# Schematic.net
KiCad netlist of a schematic drawn in Altium Designer
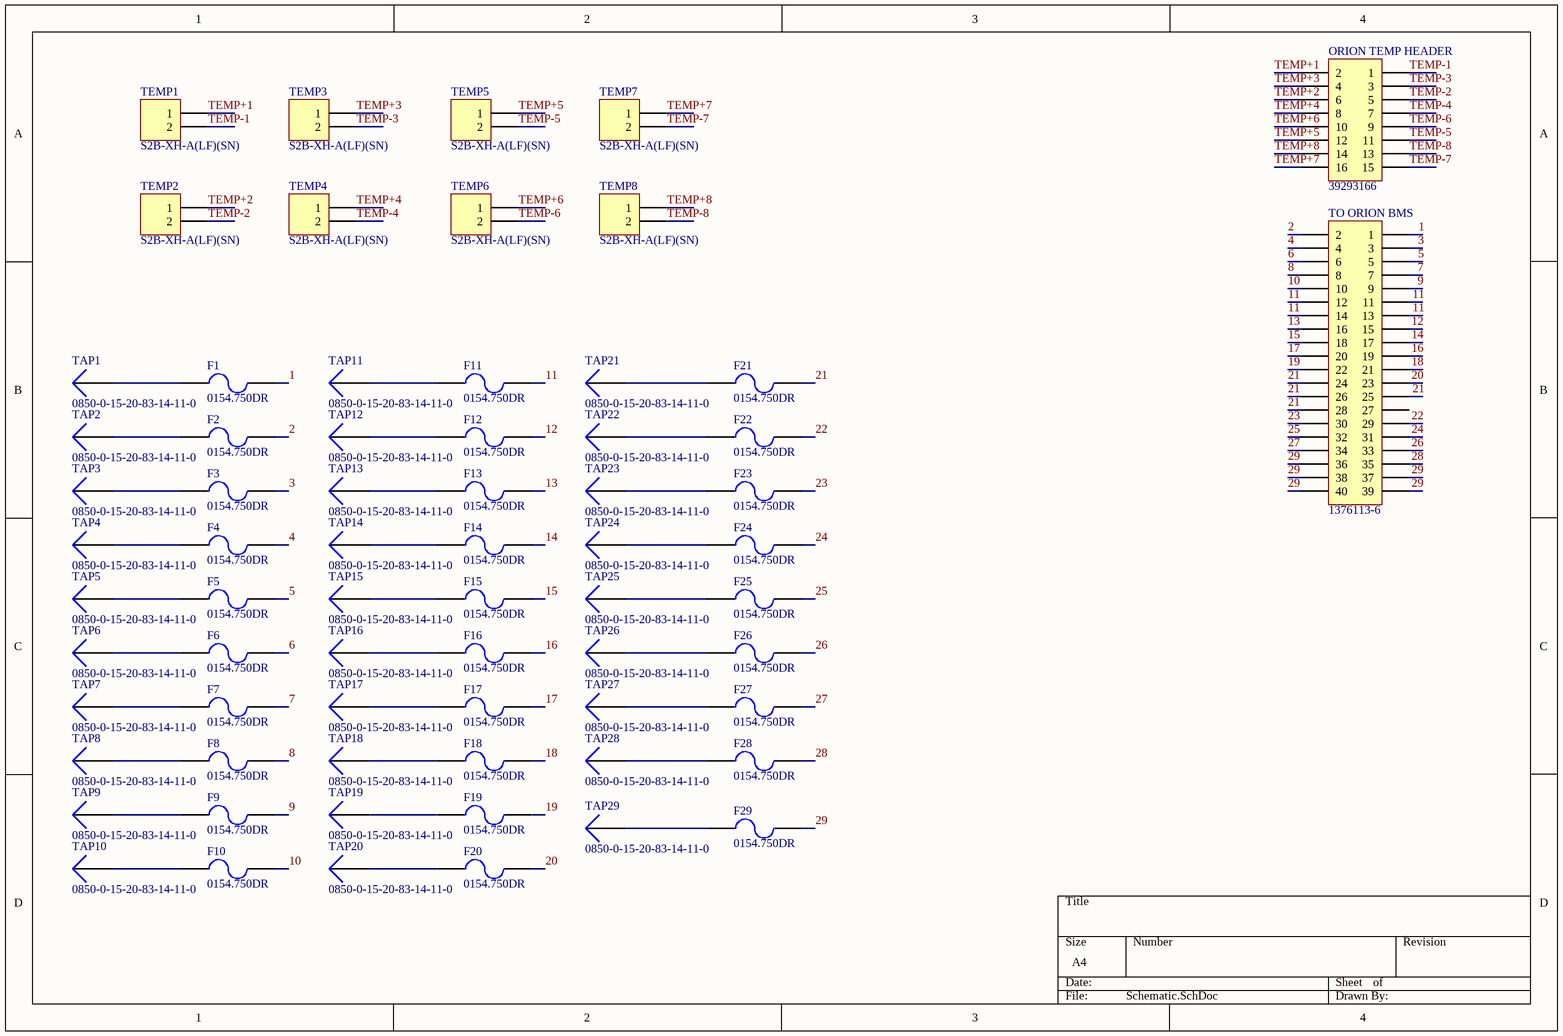
[diagram p0: Schematic.SchDoc]

(export (version "E")
  (design (tool "Eeschema 10.0.6"))
  (components
    (comp (ref "F1")
      (value "0154.750DR")
      (footprint "Omni BLOK 0154")
      (description "FUSE BOARD MNT 750MA 125VAC/VDC")
      (fields
        (field (name "MANUFACTURER") "LittelFuse Inc")
        (field (name "DIGIKEY PART NUMBER") "F1221CT-ND")
      )
      (libsource (lib "ts_20-standard-library") (part "Fuse"))
    )
    (comp (ref "F2")
      (value "0154.750DR")
      (footprint "Omni BLOK 0154")
      (description "FUSE BOARD MNT 750MA 125VAC/VDC")
      (fields
        (field (name "MANUFACTURER") "LittelFuse Inc")
        (field (name "DIGIKEY PART NUMBER") "F1221CT-ND")
      )
      (libsource (lib "ts_20-standard-library") (part "Fuse"))
    )
    (comp (ref "F3")
      (value "0154.750DR")
      (footprint "Omni BLOK 0154")
      (description "FUSE BOARD MNT 750MA 125VAC/VDC")
      (fields
        (field (name "MANUFACTURER") "LittelFuse Inc")
        (field (name "DIGIKEY PART NUMBER") "F1221CT-ND")
      )
      (libsource (lib "ts_20-standard-library") (part "Fuse"))
    )
    (comp (ref "F4")
      (value "0154.750DR")
      (footprint "Omni BLOK 0154")
      (description "FUSE BOARD MNT 750MA 125VAC/VDC")
      (fields
        (field (name "MANUFACTURER") "LittelFuse Inc")
        (field (name "DIGIKEY PART NUMBER") "F1221CT-ND")
      )
      (libsource (lib "ts_20-standard-library") (part "Fuse"))
    )
    (comp (ref "F5")
      (value "0154.750DR")
      (footprint "Omni BLOK 0154")
      (description "FUSE BOARD MNT 750MA 125VAC/VDC")
      (fields
        (field (name "MANUFACTURER") "LittelFuse Inc")
        (field (name "DIGIKEY PART NUMBER") "F1221CT-ND")
      )
      (libsource (lib "ts_20-standard-library") (part "Fuse"))
    )
    (comp (ref "F6")
      (value "0154.750DR")
      (footprint "Omni BLOK 0154")
      (description "FUSE BOARD MNT 750MA 125VAC/VDC")
      (fields
        (field (name "MANUFACTURER") "LittelFuse Inc")
        (field (name "DIGIKEY PART NUMBER") "F1221CT-ND")
      )
      (libsource (lib "ts_20-standard-library") (part "Fuse"))
    )
    (comp (ref "F7")
      (value "0154.750DR")
      (footprint "Omni BLOK 0154")
      (description "FUSE BOARD MNT 750MA 125VAC/VDC")
      (fields
        (field (name "MANUFACTURER") "LittelFuse Inc")
        (field (name "DIGIKEY PART NUMBER") "F1221CT-ND")
      )
      (libsource (lib "ts_20-standard-library") (part "Fuse"))
    )
    (comp (ref "F8")
      (value "0154.750DR")
      (footprint "Omni BLOK 0154")
      (description "FUSE BOARD MNT 750MA 125VAC/VDC")
      (fields
        (field (name "MANUFACTURER") "LittelFuse Inc")
        (field (name "DIGIKEY PART NUMBER") "F1221CT-ND")
      )
      (libsource (lib "ts_20-standard-library") (part "Fuse"))
    )
    (comp (ref "F9")
      (value "0154.750DR")
      (footprint "Omni BLOK 0154")
      (description "FUSE BOARD MNT 750MA 125VAC/VDC")
      (fields
        (field (name "MANUFACTURER") "LittelFuse Inc")
        (field (name "DIGIKEY PART NUMBER") "F1221CT-ND")
      )
      (libsource (lib "ts_20-standard-library") (part "Fuse"))
    )
    (comp (ref "F10")
      (value "0154.750DR")
      (footprint "Omni BLOK 0154")
      (description "FUSE BOARD MNT 750MA 125VAC/VDC")
      (fields
        (field (name "MANUFACTURER") "LittelFuse Inc")
        (field (name "DIGIKEY PART NUMBER") "F1221CT-ND")
      )
      (libsource (lib "ts_20-standard-library") (part "Fuse"))
    )
    (comp (ref "F11")
      (value "0154.750DR")
      (footprint "Omni BLOK 0154")
      (description "FUSE BOARD MNT 750MA 125VAC/VDC")
      (fields
        (field (name "MANUFACTURER") "LittelFuse Inc")
        (field (name "DIGIKEY PART NUMBER") "F1221CT-ND")
      )
      (libsource (lib "ts_20-standard-library") (part "Fuse"))
    )
    (comp (ref "F12")
      (value "0154.750DR")
      (footprint "Omni BLOK 0154")
      (description "FUSE BOARD MNT 750MA 125VAC/VDC")
      (fields
        (field (name "MANUFACTURER") "LittelFuse Inc")
        (field (name "DIGIKEY PART NUMBER") "F1221CT-ND")
      )
      (libsource (lib "ts_20-standard-library") (part "Fuse"))
    )
    (comp (ref "F13")
      (value "0154.750DR")
      (footprint "Omni BLOK 0154")
      (description "FUSE BOARD MNT 750MA 125VAC/VDC")
      (fields
        (field (name "MANUFACTURER") "LittelFuse Inc")
        (field (name "DIGIKEY PART NUMBER") "F1221CT-ND")
      )
      (libsource (lib "ts_20-standard-library") (part "Fuse"))
    )
    (comp (ref "F14")
      (value "0154.750DR")
      (footprint "Omni BLOK 0154")
      (description "FUSE BOARD MNT 750MA 125VAC/VDC")
      (fields
        (field (name "MANUFACTURER") "LittelFuse Inc")
        (field (name "DIGIKEY PART NUMBER") "F1221CT-ND")
      )
      (libsource (lib "ts_20-standard-library") (part "Fuse"))
    )
    (comp (ref "F15")
      (value "0154.750DR")
      (footprint "Omni BLOK 0154")
      (description "FUSE BOARD MNT 750MA 125VAC/VDC")
      (fields
        (field (name "MANUFACTURER") "LittelFuse Inc")
        (field (name "DIGIKEY PART NUMBER") "F1221CT-ND")
      )
      (libsource (lib "ts_20-standard-library") (part "Fuse"))
    )
    (comp (ref "F16")
      (value "0154.750DR")
      (footprint "Omni BLOK 0154")
      (description "FUSE BOARD MNT 750MA 125VAC/VDC")
      (fields
        (field (name "MANUFACTURER") "LittelFuse Inc")
        (field (name "DIGIKEY PART NUMBER") "F1221CT-ND")
      )
      (libsource (lib "ts_20-standard-library") (part "Fuse"))
    )
    (comp (ref "F17")
      (value "0154.750DR")
      (footprint "Omni BLOK 0154")
      (description "FUSE BOARD MNT 750MA 125VAC/VDC")
      (fields
        (field (name "MANUFACTURER") "LittelFuse Inc")
        (field (name "DIGIKEY PART NUMBER") "F1221CT-ND")
      )
      (libsource (lib "ts_20-standard-library") (part "Fuse"))
    )
    (comp (ref "F18")
      (value "0154.750DR")
      (footprint "Omni BLOK 0154")
      (description "FUSE BOARD MNT 750MA 125VAC/VDC")
      (fields
        (field (name "MANUFACTURER") "LittelFuse Inc")
        (field (name "DIGIKEY PART NUMBER") "F1221CT-ND")
      )
      (libsource (lib "ts_20-standard-library") (part "Fuse"))
    )
    (comp (ref "F19")
      (value "0154.750DR")
      (footprint "Omni BLOK 0154")
      (description "FUSE BOARD MNT 750MA 125VAC/VDC")
      (fields
        (field (name "MANUFACTURER") "LittelFuse Inc")
        (field (name "DIGIKEY PART NUMBER") "F1221CT-ND")
      )
      (libsource (lib "ts_20-standard-library") (part "Fuse"))
    )
    (comp (ref "F20")
      (value "0154.750DR")
      (footprint "Omni BLOK 0154")
      (description "FUSE BOARD MNT 750MA 125VAC/VDC")
      (fields
        (field (name "MANUFACTURER") "LittelFuse Inc")
        (field (name "DIGIKEY PART NUMBER") "F1221CT-ND")
      )
      (libsource (lib "ts_20-standard-library") (part "Fuse"))
    )
    (comp (ref "F21")
      (value "0154.750DR")
      (footprint "Omni BLOK 0154")
      (description "FUSE BOARD MNT 750MA 125VAC/VDC")
      (fields
        (field (name "MANUFACTURER") "LittelFuse Inc")
        (field (name "DIGIKEY PART NUMBER") "F1221CT-ND")
      )
      (libsource (lib "ts_20-standard-library") (part "Fuse"))
    )
    (comp (ref "F22")
      (value "0154.750DR")
      (footprint "Omni BLOK 0154")
      (description "FUSE BOARD MNT 750MA 125VAC/VDC")
      (fields
        (field (name "MANUFACTURER") "LittelFuse Inc")
        (field (name "DIGIKEY PART NUMBER") "F1221CT-ND")
      )
      (libsource (lib "ts_20-standard-library") (part "Fuse"))
    )
    (comp (ref "F23")
      (value "0154.750DR")
      (footprint "Omni BLOK 0154")
      (description "FUSE BOARD MNT 750MA 125VAC/VDC")
      (fields
        (field (name "MANUFACTURER") "LittelFuse Inc")
        (field (name "DIGIKEY PART NUMBER") "F1221CT-ND")
      )
      (libsource (lib "ts_20-standard-library") (part "Fuse"))
    )
    (comp (ref "F24")
      (value "0154.750DR")
      (footprint "Omni BLOK 0154")
      (description "FUSE BOARD MNT 750MA 125VAC/VDC")
      (fields
        (field (name "MANUFACTURER") "LittelFuse Inc")
        (field (name "DIGIKEY PART NUMBER") "F1221CT-ND")
      )
      (libsource (lib "ts_20-standard-library") (part "Fuse"))
    )
    (comp (ref "F25")
      (value "0154.750DR")
      (footprint "Omni BLOK 0154")
      (description "FUSE BOARD MNT 750MA 125VAC/VDC")
      (fields
        (field (name "MANUFACTURER") "LittelFuse Inc")
        (field (name "DIGIKEY PART NUMBER") "F1221CT-ND")
      )
      (libsource (lib "ts_20-standard-library") (part "Fuse"))
    )
    (comp (ref "F26")
      (value "0154.750DR")
      (footprint "Omni BLOK 0154")
      (description "FUSE BOARD MNT 750MA 125VAC/VDC")
      (fields
        (field (name "MANUFACTURER") "LittelFuse Inc")
        (field (name "DIGIKEY PART NUMBER") "F1221CT-ND")
      )
      (libsource (lib "ts_20-standard-library") (part "Fuse"))
    )
    (comp (ref "F27")
      (value "0154.750DR")
      (footprint "Omni BLOK 0154")
      (description "FUSE BOARD MNT 750MA 125VAC/VDC")
      (fields
        (field (name "MANUFACTURER") "LittelFuse Inc")
        (field (name "DIGIKEY PART NUMBER") "F1221CT-ND")
      )
      (libsource (lib "ts_20-standard-library") (part "Fuse"))
    )
    (comp (ref "F28")
      (value "0154.750DR")
      (footprint "Omni BLOK 0154")
      (description "FUSE BOARD MNT 750MA 125VAC/VDC")
      (fields
        (field (name "MANUFACTURER") "LittelFuse Inc")
        (field (name "DIGIKEY PART NUMBER") "F1221CT-ND")
      )
      (libsource (lib "ts_20-standard-library") (part "Fuse"))
    )
    (comp (ref "F29")
      (value "0154.750DR")
      (footprint "Omni BLOK 0154")
      (description "FUSE BOARD MNT 750MA 125VAC/VDC")
      (fields
        (field (name "MANUFACTURER") "LittelFuse Inc")
        (field (name "DIGIKEY PART NUMBER") "F1221CT-ND")
      )
      (libsource (lib "ts_20-standard-library") (part "Fuse"))
    )
    (comp (ref "ORION TEMP HEADER")
      (value "39293166")
      (footprint "39293166")
      (fields (field (name "DIGIKEY PART NUMBER") "WM3850-ND") (field (name "CONTACT") "Tin"))
      (libsource (lib "ts_20-standard-connectors") (part "16"))
    )
    (comp (ref "TAP1")
      (value "0850-0-15-20-83-14-11-0")
      (footprint "0850-0-15-20-83-14-11-0")
      (fields (field (name "DIGIKEY PART NUMBER") "ED90436-ND") (field (name "CONTACT") "Gold"))
      (libsource (lib "ts_20-standard-connectors") (part "0850-0-15-20-83-14-11-0"))
    )
    (comp (ref "TAP2")
      (value "0850-0-15-20-83-14-11-0")
      (footprint "0850-0-15-20-83-14-11-0")
      (fields (field (name "DIGIKEY PART NUMBER") "ED90436-ND") (field (name "CONTACT") "Gold"))
      (libsource (lib "ts_20-standard-connectors") (part "0850-0-15-20-83-14-11-0"))
    )
    (comp (ref "TAP3")
      (value "0850-0-15-20-83-14-11-0")
      (footprint "0850-0-15-20-83-14-11-0")
      (fields (field (name "DIGIKEY PART NUMBER") "ED90436-ND") (field (name "CONTACT") "Gold"))
      (libsource (lib "ts_20-standard-connectors") (part "0850-0-15-20-83-14-11-0"))
    )
    (comp (ref "TAP4")
      (value "0850-0-15-20-83-14-11-0")
      (footprint "0850-0-15-20-83-14-11-0")
      (fields (field (name "DIGIKEY PART NUMBER") "ED90436-ND") (field (name "CONTACT") "Gold"))
      (libsource (lib "ts_20-standard-connectors") (part "0850-0-15-20-83-14-11-0"))
    )
    (comp (ref "TAP5")
      (value "0850-0-15-20-83-14-11-0")
      (footprint "0850-0-15-20-83-14-11-0")
      (fields (field (name "DIGIKEY PART NUMBER") "ED90436-ND") (field (name "CONTACT") "Gold"))
      (libsource (lib "ts_20-standard-connectors") (part "0850-0-15-20-83-14-11-0"))
    )
    (comp (ref "TAP6")
      (value "0850-0-15-20-83-14-11-0")
      (footprint "0850-0-15-20-83-14-11-0")
      (fields (field (name "DIGIKEY PART NUMBER") "ED90436-ND") (field (name "CONTACT") "Gold"))
      (libsource (lib "ts_20-standard-connectors") (part "0850-0-15-20-83-14-11-0"))
    )
    (comp (ref "TAP7")
      (value "0850-0-15-20-83-14-11-0")
      (footprint "0850-0-15-20-83-14-11-0")
      (fields (field (name "DIGIKEY PART NUMBER") "ED90436-ND") (field (name "CONTACT") "Gold"))
      (libsource (lib "ts_20-standard-connectors") (part "0850-0-15-20-83-14-11-0"))
    )
    (comp (ref "TAP8")
      (value "0850-0-15-20-83-14-11-0")
      (footprint "0850-0-15-20-83-14-11-0")
      (fields (field (name "DIGIKEY PART NUMBER") "ED90436-ND") (field (name "CONTACT") "Gold"))
      (libsource (lib "ts_20-standard-connectors") (part "0850-0-15-20-83-14-11-0"))
    )
    (comp (ref "TAP9")
      (value "0850-0-15-20-83-14-11-0")
      (footprint "0850-0-15-20-83-14-11-0")
      (fields (field (name "DIGIKEY PART NUMBER") "ED90436-ND") (field (name "CONTACT") "Gold"))
      (libsource (lib "ts_20-standard-connectors") (part "0850-0-15-20-83-14-11-0"))
    )
    (comp (ref "TAP10")
      (value "0850-0-15-20-83-14-11-0")
      (footprint "0850-0-15-20-83-14-11-0")
      (fields (field (name "DIGIKEY PART NUMBER") "ED90436-ND") (field (name "CONTACT") "Gold"))
      (libsource (lib "ts_20-standard-connectors") (part "0850-0-15-20-83-14-11-0"))
    )
    (comp (ref "TAP11")
      (value "0850-0-15-20-83-14-11-0")
      (footprint "0850-0-15-20-83-14-11-0")
      (fields (field (name "DIGIKEY PART NUMBER") "ED90436-ND") (field (name "CONTACT") "Gold"))
      (libsource (lib "ts_20-standard-connectors") (part "0850-0-15-20-83-14-11-0"))
    )
    (comp (ref "TAP12")
      (value "0850-0-15-20-83-14-11-0")
      (footprint "0850-0-15-20-83-14-11-0")
      (fields (field (name "DIGIKEY PART NUMBER") "ED90436-ND") (field (name "CONTACT") "Gold"))
      (libsource (lib "ts_20-standard-connectors") (part "0850-0-15-20-83-14-11-0"))
    )
    (comp (ref "TAP13")
      (value "0850-0-15-20-83-14-11-0")
      (footprint "0850-0-15-20-83-14-11-0")
      (fields (field (name "DIGIKEY PART NUMBER") "ED90436-ND") (field (name "CONTACT") "Gold"))
      (libsource (lib "ts_20-standard-connectors") (part "0850-0-15-20-83-14-11-0"))
    )
    (comp (ref "TAP14")
      (value "0850-0-15-20-83-14-11-0")
      (footprint "0850-0-15-20-83-14-11-0")
      (fields (field (name "DIGIKEY PART NUMBER") "ED90436-ND") (field (name "CONTACT") "Gold"))
      (libsource (lib "ts_20-standard-connectors") (part "0850-0-15-20-83-14-11-0"))
    )
    (comp (ref "TAP15")
      (value "0850-0-15-20-83-14-11-0")
      (footprint "0850-0-15-20-83-14-11-0")
      (fields (field (name "DIGIKEY PART NUMBER") "ED90436-ND") (field (name "CONTACT") "Gold"))
      (libsource (lib "ts_20-standard-connectors") (part "0850-0-15-20-83-14-11-0"))
    )
    (comp (ref "TAP16")
      (value "0850-0-15-20-83-14-11-0")
      (footprint "0850-0-15-20-83-14-11-0")
      (fields (field (name "DIGIKEY PART NUMBER") "ED90436-ND") (field (name "CONTACT") "Gold"))
      (libsource (lib "ts_20-standard-connectors") (part "0850-0-15-20-83-14-11-0"))
    )
    (comp (ref "TAP17")
      (value "0850-0-15-20-83-14-11-0")
      (footprint "0850-0-15-20-83-14-11-0")
      (fields (field (name "DIGIKEY PART NUMBER") "ED90436-ND") (field (name "CONTACT") "Gold"))
      (libsource (lib "ts_20-standard-connectors") (part "0850-0-15-20-83-14-11-0"))
    )
    (comp (ref "TAP18")
      (value "0850-0-15-20-83-14-11-0")
      (footprint "0850-0-15-20-83-14-11-0")
      (fields (field (name "DIGIKEY PART NUMBER") "ED90436-ND") (field (name "CONTACT") "Gold"))
      (libsource (lib "ts_20-standard-connectors") (part "0850-0-15-20-83-14-11-0"))
    )
    (comp (ref "TAP19")
      (value "0850-0-15-20-83-14-11-0")
      (footprint "0850-0-15-20-83-14-11-0")
      (fields (field (name "DIGIKEY PART NUMBER") "ED90436-ND") (field (name "CONTACT") "Gold"))
      (libsource (lib "ts_20-standard-connectors") (part "0850-0-15-20-83-14-11-0"))
    )
    (comp (ref "TAP20")
      (value "0850-0-15-20-83-14-11-0")
      (footprint "0850-0-15-20-83-14-11-0")
      (fields (field (name "DIGIKEY PART NUMBER") "ED90436-ND") (field (name "CONTACT") "Gold"))
      (libsource (lib "ts_20-standard-connectors") (part "0850-0-15-20-83-14-11-0"))
    )
    (comp (ref "TAP21")
      (value "0850-0-15-20-83-14-11-0")
      (footprint "0850-0-15-20-83-14-11-0")
      (fields (field (name "DIGIKEY PART NUMBER") "ED90436-ND") (field (name "CONTACT") "Gold"))
      (libsource (lib "ts_20-standard-connectors") (part "0850-0-15-20-83-14-11-0"))
    )
    (comp (ref "TAP22")
      (value "0850-0-15-20-83-14-11-0")
      (footprint "0850-0-15-20-83-14-11-0")
      (fields (field (name "DIGIKEY PART NUMBER") "ED90436-ND") (field (name "CONTACT") "Gold"))
      (libsource (lib "ts_20-standard-connectors") (part "0850-0-15-20-83-14-11-0"))
    )
    (comp (ref "TAP23")
      (value "0850-0-15-20-83-14-11-0")
      (footprint "0850-0-15-20-83-14-11-0")
      (fields (field (name "DIGIKEY PART NUMBER") "ED90436-ND") (field (name "CONTACT") "Gold"))
      (libsource (lib "ts_20-standard-connectors") (part "0850-0-15-20-83-14-11-0"))
    )
    (comp (ref "TAP24")
      (value "0850-0-15-20-83-14-11-0")
      (footprint "0850-0-15-20-83-14-11-0")
      (fields (field (name "DIGIKEY PART NUMBER") "ED90436-ND") (field (name "CONTACT") "Gold"))
      (libsource (lib "ts_20-standard-connectors") (part "0850-0-15-20-83-14-11-0"))
    )
    (comp (ref "TAP25")
      (value "0850-0-15-20-83-14-11-0")
      (footprint "0850-0-15-20-83-14-11-0")
      (fields (field (name "DIGIKEY PART NUMBER") "ED90436-ND") (field (name "CONTACT") "Gold"))
      (libsource (lib "ts_20-standard-connectors") (part "0850-0-15-20-83-14-11-0"))
    )
    (comp (ref "TAP26")
      (value "0850-0-15-20-83-14-11-0")
      (footprint "0850-0-15-20-83-14-11-0")
      (fields (field (name "DIGIKEY PART NUMBER") "ED90436-ND") (field (name "CONTACT") "Gold"))
      (libsource (lib "ts_20-standard-connectors") (part "0850-0-15-20-83-14-11-0"))
    )
    (comp (ref "TAP27")
      (value "0850-0-15-20-83-14-11-0")
      (footprint "0850-0-15-20-83-14-11-0")
      (fields (field (name "DIGIKEY PART NUMBER") "ED90436-ND") (field (name "CONTACT") "Gold"))
      (libsource (lib "ts_20-standard-connectors") (part "0850-0-15-20-83-14-11-0"))
    )
    (comp (ref "TAP28")
      (value "0850-0-15-20-83-14-11-0")
      (footprint "0850-0-15-20-83-14-11-0")
      (fields (field (name "DIGIKEY PART NUMBER") "ED90436-ND") (field (name "CONTACT") "Gold"))
      (libsource (lib "ts_20-standard-connectors") (part "0850-0-15-20-83-14-11-0"))
    )
    (comp (ref "TAP29")
      (value "0850-0-15-20-83-14-11-0")
      (footprint "0850-0-15-20-83-14-11-0")
      (fields (field (name "DIGIKEY PART NUMBER") "ED90436-ND") (field (name "CONTACT") "Gold"))
      (libsource (lib "ts_20-standard-connectors") (part "0850-0-15-20-83-14-11-0"))
    )
    (comp (ref "TEMP1") (value "S2B-XH-A(LF)(SN)") (libsource (lib "JST") (part "S2B-XH-A(LF)(SN)")))
    (comp (ref "TEMP2") (value "S2B-XH-A(LF)(SN)") (libsource (lib "JST") (part "S2B-XH-A(LF)(SN)")))
    (comp (ref "TEMP3") (value "S2B-XH-A(LF)(SN)") (libsource (lib "JST") (part "S2B-XH-A(LF)(SN)")))
    (comp (ref "TEMP4") (value "S2B-XH-A(LF)(SN)") (libsource (lib "JST") (part "S2B-XH-A(LF)(SN)")))
    (comp (ref "TEMP5") (value "S2B-XH-A(LF)(SN)") (libsource (lib "JST") (part "S2B-XH-A(LF)(SN)")))
    (comp (ref "TEMP6") (value "S2B-XH-A(LF)(SN)") (libsource (lib "JST") (part "S2B-XH-A(LF)(SN)")))
    (comp (ref "TEMP7") (value "S2B-XH-A(LF)(SN)") (libsource (lib "JST") (part "S2B-XH-A(LF)(SN)")))
    (comp (ref "TEMP8") (value "S2B-XH-A(LF)(SN)") (libsource (lib "JST") (part "S2B-XH-A(LF)(SN)")))
    (comp (ref "TO ORION BMS")
      (value "1376113-6")
      (footprint "1376113-6")
      (fields (field (name "DIGIKEY PART NUMBER") "1376113-6-ND") (field (name "CONTACT") "Gold"))
      (libsource (lib "ts_20-standard-connectors") (part "1376113-6"))
    )
  )
  (nets
    (net (code "1") (name "/1") (class "Default")
      (node (ref "F1") (pin "2") (pinfunction "2_2") (pintype "passive"))
      (node (ref "TO ORION BMS") (pin "1") (pinfunction "1_1") (pintype "passive"))
    )
    (net (code "2") (name "/2") (class "Default")
      (node (ref "F2") (pin "2") (pinfunction "2_2") (pintype "passive"))
      (node (ref "TO ORION BMS") (pin "2") (pinfunction "2_2") (pintype "passive"))
    )
    (net (code "3") (name "/3") (class "Default")
      (node (ref "F3") (pin "2") (pinfunction "2_2") (pintype "passive"))
      (node (ref "TO ORION BMS") (pin "3") (pinfunction "3_3") (pintype "passive"))
    )
    (net (code "4") (name "/4") (class "Default")
      (node (ref "F4") (pin "2") (pinfunction "2_2") (pintype "passive"))
      (node (ref "TO ORION BMS") (pin "4") (pinfunction "4_4") (pintype "passive"))
    )
    (net (code "5") (name "/5") (class "Default")
      (node (ref "F5") (pin "2") (pinfunction "2_2") (pintype "passive"))
      (node (ref "TO ORION BMS") (pin "5") (pinfunction "5_5") (pintype "passive"))
    )
    (net (code "6") (name "/6") (class "Default")
      (node (ref "F6") (pin "2") (pinfunction "2_2") (pintype "passive"))
      (node (ref "TO ORION BMS") (pin "6") (pinfunction "6_6") (pintype "passive"))
    )
    (net (code "7") (name "/7") (class "Default")
      (node (ref "F7") (pin "2") (pinfunction "2_2") (pintype "passive"))
      (node (ref "TO ORION BMS") (pin "7") (pinfunction "7_7") (pintype "passive"))
    )
    (net (code "8") (name "/8") (class "Default")
      (node (ref "F8") (pin "2") (pinfunction "2_2") (pintype "passive"))
      (node (ref "TO ORION BMS") (pin "8") (pinfunction "8_8") (pintype "passive"))
    )
    (net (code "9") (name "/9") (class "Default")
      (node (ref "F9") (pin "2") (pinfunction "2_2") (pintype "passive"))
      (node (ref "TO ORION BMS") (pin "9") (pinfunction "9_9") (pintype "passive"))
    )
    (net (code "10") (name "/10") (class "Default")
      (node (ref "F10") (pin "2") (pinfunction "2_2") (pintype "passive"))
      (node (ref "TO ORION BMS") (pin "10") (pinfunction "10_10") (pintype "passive"))
    )
    (net (code "11") (name "/11") (class "Default")
      (node (ref "F11") (pin "2") (pinfunction "2_2") (pintype "passive"))
      (node (ref "TO ORION BMS") (pin "11") (pinfunction "11_11") (pintype "passive"))
      (node (ref "TO ORION BMS") (pin "12") (pinfunction "12_12") (pintype "passive"))
      (node (ref "TO ORION BMS") (pin "13") (pinfunction "13_13") (pintype "passive"))
      (node (ref "TO ORION BMS") (pin "14") (pinfunction "14_14") (pintype "passive"))
    )
    (net (code "12") (name "/12") (class "Default")
      (node (ref "F12") (pin "2") (pinfunction "2_2") (pintype "passive"))
      (node (ref "TO ORION BMS") (pin "15") (pinfunction "15_15") (pintype "passive"))
    )
    (net (code "13") (name "/13") (class "Default")
      (node (ref "F13") (pin "2") (pinfunction "2_2") (pintype "passive"))
      (node (ref "TO ORION BMS") (pin "16") (pinfunction "16_16") (pintype "passive"))
    )
    (net (code "14") (name "/14") (class "Default")
      (node (ref "F14") (pin "2") (pinfunction "2_2") (pintype "passive"))
      (node (ref "TO ORION BMS") (pin "17") (pinfunction "17_17") (pintype "passive"))
    )
    (net (code "15") (name "/15") (class "Default")
      (node (ref "F15") (pin "2") (pinfunction "2_2") (pintype "passive"))
      (node (ref "TO ORION BMS") (pin "18") (pinfunction "18_18") (pintype "passive"))
    )
    (net (code "16") (name "/16") (class "Default")
      (node (ref "F16") (pin "2") (pinfunction "2_2") (pintype "passive"))
      (node (ref "TO ORION BMS") (pin "19") (pinfunction "19_19") (pintype "passive"))
    )
    (net (code "17") (name "/17") (class "Default")
      (node (ref "F17") (pin "2") (pinfunction "2_2") (pintype "passive"))
      (node (ref "TO ORION BMS") (pin "20") (pinfunction "20_20") (pintype "passive"))
    )
    (net (code "18") (name "/18") (class "Default")
      (node (ref "F18") (pin "2") (pinfunction "2_2") (pintype "passive"))
      (node (ref "TO ORION BMS") (pin "21") (pinfunction "21_21") (pintype "passive"))
    )
    (net (code "19") (name "/19") (class "Default")
      (node (ref "F19") (pin "2") (pinfunction "2_2") (pintype "passive"))
      (node (ref "TO ORION BMS") (pin "22") (pinfunction "22_22") (pintype "passive"))
    )
    (net (code "20") (name "/20") (class "Default")
      (node (ref "F20") (pin "2") (pinfunction "2_2") (pintype "passive"))
      (node (ref "TO ORION BMS") (pin "23") (pinfunction "23_23") (pintype "passive"))
    )
    (net (code "21") (name "/21") (class "Default")
      (node (ref "F21") (pin "2") (pinfunction "2_2") (pintype "passive"))
      (node (ref "TO ORION BMS") (pin "24") (pinfunction "24_24") (pintype "passive"))
      (node (ref "TO ORION BMS") (pin "25") (pinfunction "25_25") (pintype "passive"))
      (node (ref "TO ORION BMS") (pin "26") (pinfunction "26_26") (pintype "passive"))
      (node (ref "TO ORION BMS") (pin "28") (pinfunction "28_28") (pintype "passive"))
    )
    (net (code "22") (name "/22") (class "Default")
      (node (ref "F22") (pin "2") (pinfunction "2_2") (pintype "passive"))
      (node (ref "TO ORION BMS") (pin "29") (pinfunction "29_29") (pintype "passive"))
    )
    (net (code "23") (name "/23") (class "Default")
      (node (ref "F23") (pin "2") (pinfunction "2_2") (pintype "passive"))
      (node (ref "TO ORION BMS") (pin "30") (pinfunction "30_30") (pintype "passive"))
    )
    (net (code "24") (name "/24") (class "Default")
      (node (ref "F24") (pin "2") (pinfunction "2_2") (pintype "passive"))
      (node (ref "TO ORION BMS") (pin "31") (pinfunction "31_31") (pintype "passive"))
    )
    (net (code "25") (name "/25") (class "Default")
      (node (ref "F25") (pin "2") (pinfunction "2_2") (pintype "passive"))
      (node (ref "TO ORION BMS") (pin "32") (pinfunction "32_32") (pintype "passive"))
    )
    (net (code "26") (name "/26") (class "Default")
      (node (ref "F26") (pin "2") (pinfunction "2_2") (pintype "passive"))
      (node (ref "TO ORION BMS") (pin "33") (pinfunction "33_33") (pintype "passive"))
    )
    (net (code "27") (name "/27") (class "Default")
      (node (ref "F27") (pin "2") (pinfunction "2_2") (pintype "passive"))
      (node (ref "TO ORION BMS") (pin "34") (pinfunction "34_34") (pintype "passive"))
    )
    (net (code "28") (name "/28") (class "Default")
      (node (ref "F28") (pin "2") (pinfunction "2_2") (pintype "passive"))
      (node (ref "TO ORION BMS") (pin "35") (pinfunction "35_35") (pintype "passive"))
    )
    (net (code "29") (name "/29") (class "Default")
      (node (ref "F29") (pin "2") (pinfunction "2_2") (pintype "passive"))
      (node (ref "TO ORION BMS") (pin "36") (pinfunction "36_36") (pintype "passive"))
      (node (ref "TO ORION BMS") (pin "37") (pinfunction "37_37") (pintype "passive"))
      (node (ref "TO ORION BMS") (pin "38") (pinfunction "38_38") (pintype "passive"))
      (node (ref "TO ORION BMS") (pin "39") (pinfunction "39_39") (pintype "passive"))
      (node (ref "TO ORION BMS") (pin "40") (pinfunction "40_40") (pintype "passive"))
    )
    (net (code "30") (name "/TEMP+1") (class "Default")
      (node (ref "ORION TEMP HEADER") (pin "2") (pinfunction "2_2") (pintype "passive"))
      (node (ref "TEMP1") (pin "1") (pinfunction "1_1") (pintype "passive"))
    )
    (net (code "31") (name "/TEMP+2") (class "Default")
      (node (ref "ORION TEMP HEADER") (pin "6") (pinfunction "6_6") (pintype "passive"))
      (node (ref "TEMP2") (pin "1") (pinfunction "1_1") (pintype "passive"))
    )
    (net (code "32") (name "/TEMP+3") (class "Default")
      (node (ref "ORION TEMP HEADER") (pin "4") (pinfunction "4_4") (pintype "passive"))
      (node (ref "TEMP3") (pin "1") (pinfunction "1_1") (pintype "passive"))
    )
    (net (code "33") (name "/TEMP+4") (class "Default")
      (node (ref "ORION TEMP HEADER") (pin "8") (pinfunction "8_8") (pintype "passive"))
      (node (ref "TEMP4") (pin "1") (pinfunction "1_1") (pintype "passive"))
    )
    (net (code "34") (name "/TEMP+5") (class "Default")
      (node (ref "ORION TEMP HEADER") (pin "12") (pinfunction "12_12") (pintype "passive"))
      (node (ref "TEMP5") (pin "1") (pinfunction "1_1") (pintype "passive"))
    )
    (net (code "35") (name "/TEMP+6") (class "Default")
      (node (ref "ORION TEMP HEADER") (pin "10") (pinfunction "10_10") (pintype "passive"))
      (node (ref "TEMP6") (pin "1") (pinfunction "1_1") (pintype "passive"))
    )
    (net (code "36") (name "/TEMP+7") (class "Default")
      (node (ref "ORION TEMP HEADER") (pin "16") (pinfunction "16_16") (pintype "passive"))
      (node (ref "TEMP7") (pin "1") (pinfunction "1_1") (pintype "passive"))
    )
    (net (code "37") (name "/TEMP+8") (class "Default")
      (node (ref "ORION TEMP HEADER") (pin "14") (pinfunction "14_14") (pintype "passive"))
      (node (ref "TEMP8") (pin "1") (pinfunction "1_1") (pintype "passive"))
    )
    (net (code "38") (name "/TEMP-1") (class "Default")
      (node (ref "ORION TEMP HEADER") (pin "1") (pinfunction "1_1") (pintype "passive"))
      (node (ref "TEMP1") (pin "2") (pinfunction "2_2") (pintype "passive"))
    )
    (net (code "39") (name "/TEMP-2") (class "Default")
      (node (ref "ORION TEMP HEADER") (pin "5") (pinfunction "5_5") (pintype "passive"))
      (node (ref "TEMP2") (pin "2") (pinfunction "2_2") (pintype "passive"))
    )
    (net (code "40") (name "/TEMP-3") (class "Default")
      (node (ref "ORION TEMP HEADER") (pin "3") (pinfunction "3_3") (pintype "passive"))
      (node (ref "TEMP3") (pin "2") (pinfunction "2_2") (pintype "passive"))
    )
    (net (code "41") (name "/TEMP-4") (class "Default")
      (node (ref "ORION TEMP HEADER") (pin "7") (pinfunction "7_7") (pintype "passive"))
      (node (ref "TEMP4") (pin "2") (pinfunction "2_2") (pintype "passive"))
    )
    (net (code "42") (name "/TEMP-5") (class "Default")
      (node (ref "ORION TEMP HEADER") (pin "11") (pinfunction "11_11") (pintype "passive"))
      (node (ref "TEMP5") (pin "2") (pinfunction "2_2") (pintype "passive"))
    )
    (net (code "43") (name "/TEMP-6") (class "Default")
      (node (ref "ORION TEMP HEADER") (pin "9") (pinfunction "9_9") (pintype "passive"))
      (node (ref "TEMP6") (pin "2") (pinfunction "2_2") (pintype "passive"))
    )
    (net (code "44") (name "/TEMP-7") (class "Default")
      (node (ref "ORION TEMP HEADER") (pin "15") (pinfunction "15_15") (pintype "passive"))
      (node (ref "TEMP7") (pin "2") (pinfunction "2_2") (pintype "passive"))
    )
    (net (code "45") (name "/TEMP-8") (class "Default")
      (node (ref "ORION TEMP HEADER") (pin "13") (pinfunction "13_13") (pintype "passive"))
      (node (ref "TEMP8") (pin "2") (pinfunction "2_2") (pintype "passive"))
    )
    (net (code "46") (name "Net-(TAP1-=\"part_number\")") (class "Default")
      (node (ref "F1") (pin "1") (pinfunction "1_1") (pintype "passive"))
      (node (ref "TAP1") (pin "1") (pinfunction "=\"part_number\"_1") (pintype "passive"))
    )
    (net (code "47") (name "Net-(TAP2-=\"part_number\")") (class "Default")
      (node (ref "F2") (pin "1") (pinfunction "1_1") (pintype "passive"))
      (node (ref "TAP2") (pin "1") (pinfunction "=\"part_number\"_1") (pintype "passive"))
    )
    (net (code "48") (name "Net-(TAP3-=\"part_number\")") (class "Default")
      (node (ref "F3") (pin "1") (pinfunction "1_1") (pintype "passive"))
      (node (ref "TAP3") (pin "1") (pinfunction "=\"part_number\"_1") (pintype "passive"))
    )
    (net (code "49") (name "Net-(TAP4-=\"part_number\")") (class "Default")
      (node (ref "F4") (pin "1") (pinfunction "1_1") (pintype "passive"))
      (node (ref "TAP4") (pin "1") (pinfunction "=\"part_number\"_1") (pintype "passive"))
    )
    (net (code "50") (name "Net-(TAP5-=\"part_number\")") (class "Default")
      (node (ref "F5") (pin "1") (pinfunction "1_1") (pintype "passive"))
      (node (ref "TAP5") (pin "1") (pinfunction "=\"part_number\"_1") (pintype "passive"))
    )
    (net (code "51") (name "Net-(TAP6-=\"part_number\")") (class "Default")
      (node (ref "F6") (pin "1") (pinfunction "1_1") (pintype "passive"))
      (node (ref "TAP6") (pin "1") (pinfunction "=\"part_number\"_1") (pintype "passive"))
    )
    (net (code "52") (name "Net-(TAP7-=\"part_number\")") (class "Default")
      (node (ref "F7") (pin "1") (pinfunction "1_1") (pintype "passive"))
      (node (ref "TAP7") (pin "1") (pinfunction "=\"part_number\"_1") (pintype "passive"))
    )
    (net (code "53") (name "Net-(TAP8-=\"part_number\")") (class "Default")
      (node (ref "F8") (pin "1") (pinfunction "1_1") (pintype "passive"))
      (node (ref "TAP8") (pin "1") (pinfunction "=\"part_number\"_1") (pintype "passive"))
    )
    (net (code "54") (name "Net-(TAP9-=\"part_number\")") (class "Default")
      (node (ref "F9") (pin "1") (pinfunction "1_1") (pintype "passive"))
      (node (ref "TAP9") (pin "1") (pinfunction "=\"part_number\"_1") (pintype "passive"))
    )
    (net (code "55") (name "Net-(TAP10-=\"part_number\")") (class "Default")
      (node (ref "F10") (pin "1") (pinfunction "1_1") (pintype "passive"))
      (node (ref "TAP10") (pin "1") (pinfunction "=\"part_number\"_1") (pintype "passive"))
    )
    (net (code "56") (name "Net-(TAP11-=\"part_number\")") (class "Default")
      (node (ref "F11") (pin "1") (pinfunction "1_1") (pintype "passive"))
      (node (ref "TAP11") (pin "1") (pinfunction "=\"part_number\"_1") (pintype "passive"))
    )
    (net (code "57") (name "Net-(TAP12-=\"part_number\")") (class "Default")
      (node (ref "F12") (pin "1") (pinfunction "1_1") (pintype "passive"))
      (node (ref "TAP12") (pin "1") (pinfunction "=\"part_number\"_1") (pintype "passive"))
    )
    (net (code "58") (name "Net-(TAP13-=\"part_number\")") (class "Default")
      (node (ref "F13") (pin "1") (pinfunction "1_1") (pintype "passive"))
      (node (ref "TAP13") (pin "1") (pinfunction "=\"part_number\"_1") (pintype "passive"))
    )
    (net (code "59") (name "Net-(TAP14-=\"part_number\")") (class "Default")
      (node (ref "F14") (pin "1") (pinfunction "1_1") (pintype "passive"))
      (node (ref "TAP14") (pin "1") (pinfunction "=\"part_number\"_1") (pintype "passive"))
    )
    (net (code "60") (name "Net-(TAP15-=\"part_number\")") (class "Default")
      (node (ref "F15") (pin "1") (pinfunction "1_1") (pintype "passive"))
      (node (ref "TAP15") (pin "1") (pinfunction "=\"part_number\"_1") (pintype "passive"))
    )
    (net (code "61") (name "Net-(TAP16-=\"part_number\")") (class "Default")
      (node (ref "F16") (pin "1") (pinfunction "1_1") (pintype "passive"))
      (node (ref "TAP16") (pin "1") (pinfunction "=\"part_number\"_1") (pintype "passive"))
    )
    (net (code "62") (name "Net-(TAP17-=\"part_number\")") (class "Default")
      (node (ref "F17") (pin "1") (pinfunction "1_1") (pintype "passive"))
      (node (ref "TAP17") (pin "1") (pinfunction "=\"part_number\"_1") (pintype "passive"))
    )
    (net (code "63") (name "Net-(TAP18-=\"part_number\")") (class "Default")
      (node (ref "F18") (pin "1") (pinfunction "1_1") (pintype "passive"))
      (node (ref "TAP18") (pin "1") (pinfunction "=\"part_number\"_1") (pintype "passive"))
    )
    (net (code "64") (name "Net-(TAP19-=\"part_number\")") (class "Default")
      (node (ref "F19") (pin "1") (pinfunction "1_1") (pintype "passive"))
      (node (ref "TAP19") (pin "1") (pinfunction "=\"part_number\"_1") (pintype "passive"))
    )
    (net (code "65") (name "Net-(TAP20-=\"part_number\")") (class "Default")
      (node (ref "F20") (pin "1") (pinfunction "1_1") (pintype "passive"))
      (node (ref "TAP20") (pin "1") (pinfunction "=\"part_number\"_1") (pintype "passive"))
    )
    (net (code "66") (name "Net-(TAP21-=\"part_number\")") (class "Default")
      (node (ref "F21") (pin "1") (pinfunction "1_1") (pintype "passive"))
      (node (ref "TAP21") (pin "1") (pinfunction "=\"part_number\"_1") (pintype "passive"))
    )
    (net (code "67") (name "Net-(TAP22-=\"part_number\")") (class "Default")
      (node (ref "F22") (pin "1") (pinfunction "1_1") (pintype "passive"))
      (node (ref "TAP22") (pin "1") (pinfunction "=\"part_number\"_1") (pintype "passive"))
    )
    (net (code "68") (name "Net-(TAP23-=\"part_number\")") (class "Default")
      (node (ref "F23") (pin "1") (pinfunction "1_1") (pintype "passive"))
      (node (ref "TAP23") (pin "1") (pinfunction "=\"part_number\"_1") (pintype "passive"))
    )
    (net (code "69") (name "Net-(TAP24-=\"part_number\")") (class "Default")
      (node (ref "F24") (pin "1") (pinfunction "1_1") (pintype "passive"))
      (node (ref "TAP24") (pin "1") (pinfunction "=\"part_number\"_1") (pintype "passive"))
    )
    (net (code "70") (name "Net-(TAP25-=\"part_number\")") (class "Default")
      (node (ref "F25") (pin "1") (pinfunction "1_1") (pintype "passive"))
      (node (ref "TAP25") (pin "1") (pinfunction "=\"part_number\"_1") (pintype "passive"))
    )
    (net (code "71") (name "Net-(TAP26-=\"part_number\")") (class "Default")
      (node (ref "F26") (pin "1") (pinfunction "1_1") (pintype "passive"))
      (node (ref "TAP26") (pin "1") (pinfunction "=\"part_number\"_1") (pintype "passive"))
    )
    (net (code "72") (name "Net-(TAP27-=\"part_number\")") (class "Default")
      (node (ref "F27") (pin "1") (pinfunction "1_1") (pintype "passive"))
      (node (ref "TAP27") (pin "1") (pinfunction "=\"part_number\"_1") (pintype "passive"))
    )
    (net (code "73") (name "Net-(TAP28-=\"part_number\")") (class "Default")
      (node (ref "F28") (pin "1") (pinfunction "1_1") (pintype "passive"))
      (node (ref "TAP28") (pin "1") (pinfunction "=\"part_number\"_1") (pintype "passive"))
    )
    (net (code "74") (name "Net-(TAP29-=\"part_number\")") (class "Default")
      (node (ref "F29") (pin "1") (pinfunction "1_1") (pintype "passive"))
      (node (ref "TAP29") (pin "1") (pinfunction "=\"part_number\"_1") (pintype "passive"))
    )
    (net (code "75") (name "unconnected-(TO ORION BMS-Pad27)") (class "Default")
      (node (ref "TO ORION BMS") (pin "27") (pinfunction "27_27") (pintype "passive"))
    )
  )
)
